# SelfTestWiring.net
KiCad netlist of a schematic drawn in EAGLE
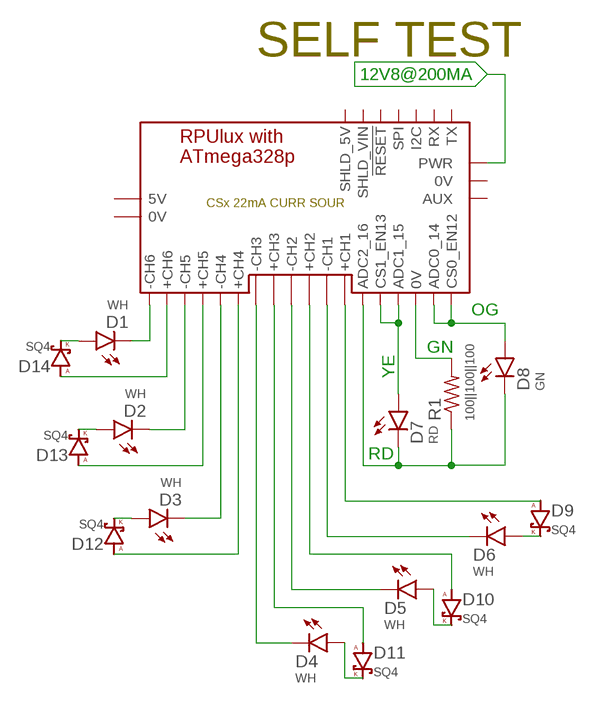
[diagram p0: schematic, sheet 1]

(export (version "E")
  (design (tool "Eeschema 10.0.6"))
  (components
    (comp (ref "D1")
      (value "WH")
      (footprint "eagle-import:LED5MM")
      (libsource (lib "eagle-import") (part "LED5MM"))
    )
    (comp (ref "D2")
      (value "WH")
      (footprint "eagle-import:LED5MM")
      (libsource (lib "eagle-import") (part "LED5MM"))
    )
    (comp (ref "D3")
      (value "WH")
      (footprint "eagle-import:LED5MM")
      (libsource (lib "eagle-import") (part "LED5MM"))
    )
    (comp (ref "D4")
      (value "WH")
      (footprint "eagle-import:LED5MM")
      (libsource (lib "eagle-import") (part "LED5MM"))
    )
    (comp (ref "D5")
      (value "WH")
      (footprint "eagle-import:LED5MM")
      (libsource (lib "eagle-import") (part "LED5MM"))
    )
    (comp (ref "D6")
      (value "WH")
      (footprint "eagle-import:LED5MM")
      (libsource (lib "eagle-import") (part "LED5MM"))
    )
    (comp (ref "D7")
      (value "RD")
      (footprint "eagle-import:LED5MM")
      (libsource (lib "eagle-import") (part "LED5MM"))
    )
    (comp (ref "D8")
      (value "GN")
      (footprint "eagle-import:LED5MM")
      (libsource (lib "eagle-import") (part "LED5MM"))
    )
    (comp (ref "D9")
      (value "SQ4")
      (footprint "eagle-import:SMA")
      (libsource (lib "eagle-import") (part "DSMA"))
    )
    (comp (ref "D10")
      (value "SQ4")
      (footprint "eagle-import:SMA")
      (libsource (lib "eagle-import") (part "DSMA"))
    )
    (comp (ref "D11")
      (value "SQ4")
      (footprint "eagle-import:SMA")
      (libsource (lib "eagle-import") (part "DSMA"))
    )
    (comp (ref "D12")
      (value "SQ4")
      (footprint "eagle-import:SMA")
      (libsource (lib "eagle-import") (part "DSMA"))
    )
    (comp (ref "D13")
      (value "SQ4")
      (footprint "eagle-import:SMA")
      (libsource (lib "eagle-import") (part "DSMA"))
    )
    (comp (ref "D14")
      (value "SQ4")
      (footprint "eagle-import:SMA")
      (libsource (lib "eagle-import") (part "DSMA"))
    )
    (comp (ref "R1")
      (value "100||100||100")
      (footprint "eagle-import:C0805(2012)")
      (libsource (lib "eagle-import") (part "R0805"))
    )
    (comp (ref "U$1")
      (value "RPULUX")
      (footprint "eagle-import:WITH_RPU_NAMES")
      (libsource (lib "eagle-import") (part "RPULUX"))
    )
  )
  (nets
    (net (code "1") (name "/GN") (class "Default")
      (node (ref "R1") (pin "2") (pinfunction "2_2") (pintype "passive"))
      (node (ref "U$1") (pin "0V@DIO2") (pinfunction "0V_0V@DIO2") (pintype "bidirectional"))
    )
    (net (code "2") (name "/OG") (class "Default")
      (node (ref "D8") (pin "A") (pinfunction "A_A") (pintype "passive"))
      (node (ref "U$1") (pin "22MA@ADC0") (pinfunction "CS0_EN12_22MA@ADC0") (pintype "bidirectional"))
      (node (ref "U$1") (pin "ADC0") (pinfunction "ADC0_14_ADC0") (pintype "bidirectional"))
    )
    (net (code "3") (name "/RD") (class "Default")
      (node (ref "D7") (pin "K") (pinfunction "K_K") (pintype "passive"))
      (node (ref "D8") (pin "K") (pinfunction "K_K") (pintype "passive"))
      (node (ref "R1") (pin "1") (pinfunction "1_1") (pintype "passive"))
      (node (ref "U$1") (pin "ADC2") (pinfunction "ADC2_16_ADC2") (pintype "bidirectional"))
    )
    (net (code "4") (name "/YE") (class "Default")
      (node (ref "D7") (pin "A") (pinfunction "A_A") (pintype "passive"))
      (node (ref "U$1") (pin "22MA@ADC1") (pinfunction "CS1_EN13_22MA@ADC1") (pintype "bidirectional"))
      (node (ref "U$1") (pin "ADC1") (pinfunction "ADC1_15_ADC1") (pintype "bidirectional"))
    )
    (net (code "5") (name "12V8@200MA") (class "Default")
      (node (ref "U$1") (pin "PWR") (pinfunction "PWR_PWR") (pintype "bidirectional"))
    )
    (net (code "6") (name "Net-(D1-PadA)") (class "Default")
      (node (ref "D1") (pin "A") (pinfunction "A_A") (pintype "passive"))
      (node (ref "D14") (pin "K") (pinfunction "K_K") (pintype "passive"))
    )
    (net (code "7") (name "Net-(D1-PadK)") (class "Default")
      (node (ref "D1") (pin "K") (pinfunction "K_K") (pintype "passive"))
      (node (ref "U$1") (pin "-CH6") (pinfunction "-CH6_-CH6") (pintype "bidirectional"))
    )
    (net (code "8") (name "Net-(D2-PadK)") (class "Default")
      (node (ref "D2") (pin "K") (pinfunction "K_K") (pintype "passive"))
      (node (ref "U$1") (pin "-CH5") (pinfunction "-CH5_-CH5") (pintype "bidirectional"))
    )
    (net (code "9") (name "Net-(D3-PadK)") (class "Default")
      (node (ref "D3") (pin "K") (pinfunction "K_K") (pintype "passive"))
      (node (ref "U$1") (pin "-CH4") (pinfunction "-CH4_-CH4") (pintype "bidirectional"))
    )
    (net (code "10") (name "Net-(D4-PadK)") (class "Default")
      (node (ref "D4") (pin "K") (pinfunction "K_K") (pintype "passive"))
      (node (ref "U$1") (pin "-CH3") (pinfunction "-CH3_-CH3") (pintype "bidirectional"))
    )
    (net (code "11") (name "Net-(D5-PadK)") (class "Default")
      (node (ref "D5") (pin "K") (pinfunction "K_K") (pintype "passive"))
      (node (ref "U$1") (pin "-CH2") (pinfunction "-CH2_-CH2") (pintype "bidirectional"))
    )
    (net (code "12") (name "Net-(D6-PadA)") (class "Default")
      (node (ref "D6") (pin "A") (pinfunction "A_A") (pintype "passive"))
      (node (ref "D9") (pin "K") (pinfunction "K_K") (pintype "passive"))
    )
    (net (code "13") (name "Net-(D6-PadK)") (class "Default")
      (node (ref "D6") (pin "K") (pinfunction "K_K") (pintype "passive"))
      (node (ref "U$1") (pin "-CH1") (pinfunction "-CH1_-CH1") (pintype "bidirectional"))
    )
    (net (code "14") (name "Net-(D9-PadA)") (class "Default")
      (node (ref "D9") (pin "A") (pinfunction "A_A") (pintype "passive"))
      (node (ref "U$1") (pin "+CH1") (pinfunction "+CH1_+CH1") (pintype "bidirectional"))
    )
    (net (code "15") (name "Net-(D10-PadA)") (class "Default")
      (node (ref "D10") (pin "A") (pinfunction "A_A") (pintype "passive"))
      (node (ref "U$1") (pin "+CH2") (pinfunction "+CH2_+CH2") (pintype "bidirectional"))
    )
    (net (code "16") (name "Net-(D10-PadK)") (class "Default")
      (node (ref "D10") (pin "K") (pinfunction "K_K") (pintype "passive"))
      (node (ref "D5") (pin "A") (pinfunction "A_A") (pintype "passive"))
    )
    (net (code "17") (name "Net-(D11-PadA)") (class "Default")
      (node (ref "D11") (pin "A") (pinfunction "A_A") (pintype "passive"))
      (node (ref "U$1") (pin "+CH3") (pinfunction "+CH3_+CH3") (pintype "bidirectional"))
    )
    (net (code "18") (name "Net-(D11-PadK)") (class "Default")
      (node (ref "D11") (pin "K") (pinfunction "K_K") (pintype "passive"))
      (node (ref "D4") (pin "A") (pinfunction "A_A") (pintype "passive"))
    )
    (net (code "19") (name "Net-(D12-PadA)") (class "Default")
      (node (ref "D12") (pin "A") (pinfunction "A_A") (pintype "passive"))
      (node (ref "U$1") (pin "+CH4") (pinfunction "+CH4_+CH4") (pintype "bidirectional"))
    )
    (net (code "20") (name "Net-(D12-PadK)") (class "Default")
      (node (ref "D12") (pin "K") (pinfunction "K_K") (pintype "passive"))
      (node (ref "D3") (pin "A") (pinfunction "A_A") (pintype "passive"))
    )
    (net (code "21") (name "Net-(D13-PadA)") (class "Default")
      (node (ref "D13") (pin "A") (pinfunction "A_A") (pintype "passive"))
      (node (ref "U$1") (pin "+CH5") (pinfunction "+CH5_+CH5") (pintype "bidirectional"))
    )
    (net (code "22") (name "Net-(D13-PadK)") (class "Default")
      (node (ref "D13") (pin "K") (pinfunction "K_K") (pintype "passive"))
      (node (ref "D2") (pin "A") (pinfunction "A_A") (pintype "passive"))
    )
    (net (code "23") (name "Net-(D14-PadA)") (class "Default")
      (node (ref "D14") (pin "A") (pinfunction "A_A") (pintype "passive"))
      (node (ref "U$1") (pin "+CH6") (pinfunction "+CH6_+CH6") (pintype "bidirectional"))
    )
    (net (code "24") (name "unconnected-(U$1-0V-Pad0V@PWR)") (class "Default")
      (node (ref "U$1") (pin "0V@PWR") (pinfunction "0V_0V@PWR") (pintype "bidirectional"))
    )
    (net (code "25") (name "unconnected-(U$1-Pad0V)") (class "Default")
      (node (ref "U$1") (pin "0V") (pinfunction "0V_0V") (pintype "bidirectional"))
    )
    (net (code "26") (name "unconnected-(U$1-Pad5V)") (class "Default")
      (node (ref "U$1") (pin "5V") (pinfunction "5V_5V") (pintype "bidirectional"))
    )
    (net (code "27") (name "unconnected-(U$1-PadAUX)") (class "Default")
      (node (ref "U$1") (pin "AUX") (pinfunction "AUX_AUX") (pintype "bidirectional"))
    )
    (net (code "28") (name "unconnected-(U$1-PadI2C)") (class "Default")
      (node (ref "U$1") (pin "I2C") (pinfunction "I2C_I2C") (pintype "bidirectional"))
    )
    (net (code "29") (name "unconnected-(U$1-PadRX)") (class "Default")
      (node (ref "U$1") (pin "RX") (pinfunction "RX_RX") (pintype "bidirectional"))
    )
    (net (code "30") (name "unconnected-(U$1-PadSHLD_5V)") (class "Default")
      (node (ref "U$1") (pin "SHLD_5V") (pinfunction "SHLD_5V_SHLD_5V") (pintype "bidirectional"))
    )
    (net (code "31") (name "unconnected-(U$1-PadSPI)") (class "Default")
      (node (ref "U$1") (pin "SPI") (pinfunction "SPI_SPI") (pintype "bidirectional"))
    )
    (net (code "32") (name "unconnected-(U$1-PadTX)") (class "Default")
      (node (ref "U$1") (pin "TX") (pinfunction "TX_TX") (pintype "bidirectional"))
    )
    (net (code "33") (name "unconnected-(U$1-SHLD_VIN-PadSHLD_VOUT)") (class "Default")
      (node (ref "U$1") (pin "SHLD_VOUT") (pinfunction "SHLD_VIN_SHLD_VOUT") (pintype "bidirectional"))
    )
    (net (code "34") (name "unconnected-(U$1-~{RESET}-Pad!RESET)") (class "Default")
      (node (ref "U$1") (pin "!RESET") (pinfunction "~{RESET}_!RESET") (pintype "bidirectional"))
    )
  )
)
